# EasyEDA_SCH_ESPHome_Inverter_2341.net
KiCad netlist of a schematic drawn in EasyEDA
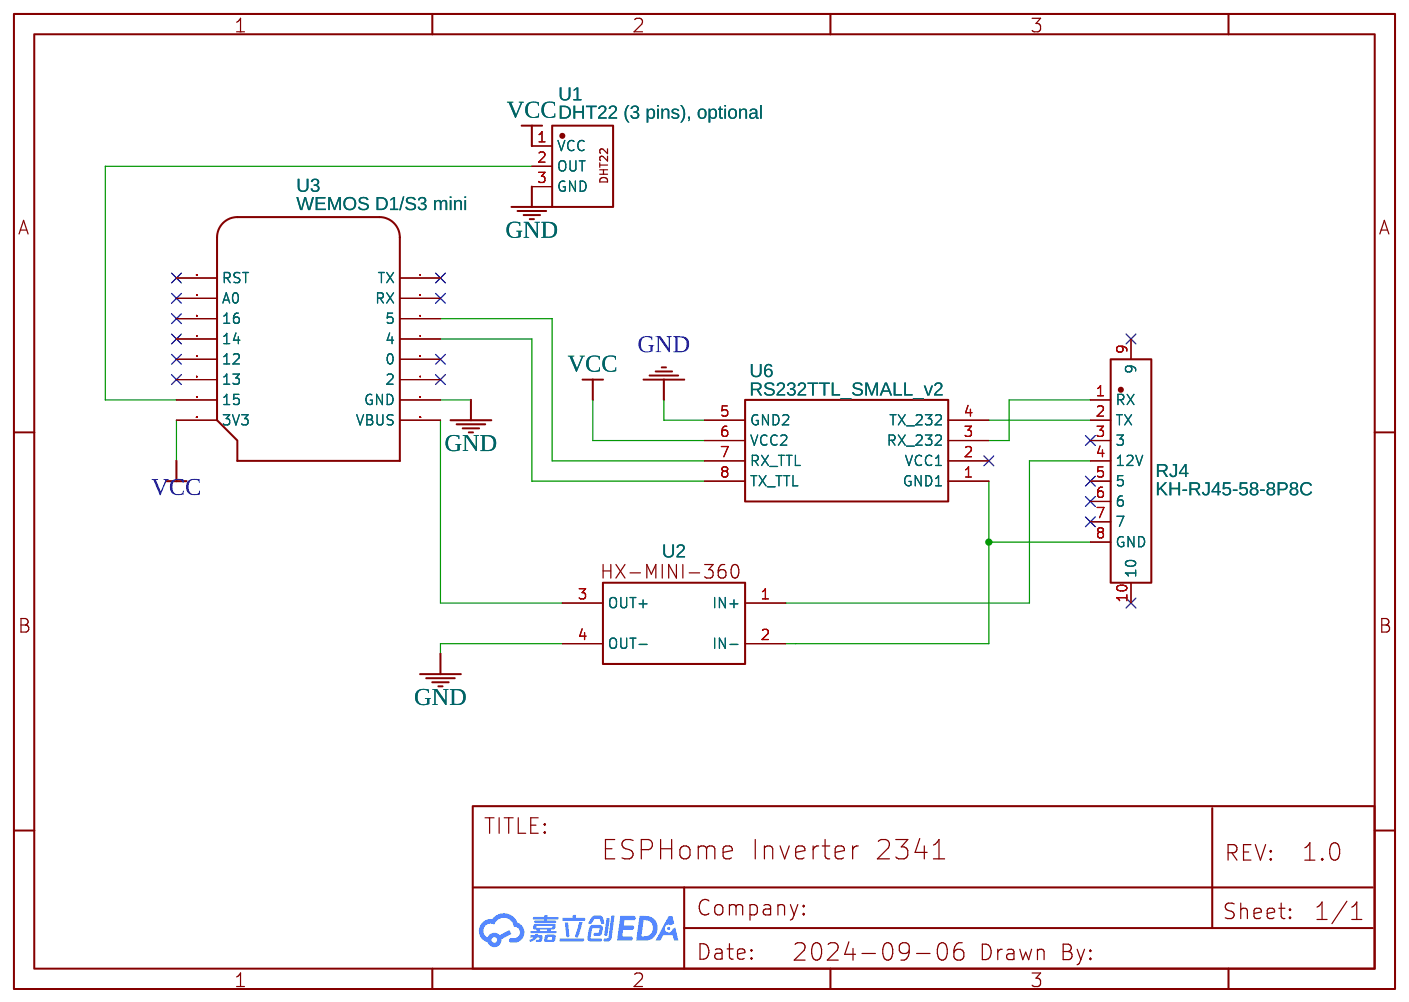
[diagram p0: schematic sheet]

(export (version "E")
  (design (tool "Eeschema 10.0.6"))
  (components
    (comp (ref "RJ4")
      (value "KH-RJ45-58-8P8C")
      (fields (field (name "Manufacturer") "kinghelm(金航标)"))
      (libsource (lib "") (part "KH-RJ45-58-8P8C"))
    )
    (comp (ref "U1")
      (value "DHT22 (3 pins), optional")
      (fields (field (name "Manufacturer Part") "DHT22 Modulo") (field (name "Manufacturer") "ASAIR AM2302"))
      (libsource (lib "") (part "DHT22 Modulo (3 pinos)"))
    )
    (comp (ref "U2") (value "HX-MINI-360 Module") (libsource (lib "") (part "HX-MINI-360 Module")))
    (comp (ref "U3")
      (value "WEMOS D1/S3 mini")
      (fields (field (name "Manufacturer Part") "WeMos D1 Mini Pro"))
      (libsource (lib "") (part "WEMOS D1 V4"))
    )
    (comp (ref "U6") (value "RS232TTL_SMALL_v2") (libsource (lib "") (part "RS232TTL_SMALL_v2")))
  )
  (nets
    (net (code "1") (name "GND") (class "Default")
      (node (ref "U1") (pin "3") (pinfunction "GND_3") (pintype "unspecified"))
      (node (ref "U2") (pin "4") (pinfunction "OUT-_4") (pintype "unspecified"))
      (node (ref "U3") (pin "GND") (pinfunction "GND_GND") (pintype "unspecified"))
      (node (ref "U6") (pin "5") (pinfunction "GND2_5") (pintype "unspecified"))
    )
    (net (code "2") (name "Net-(RJ4-12V)") (class "Default")
      (node (ref "RJ4") (pin "4") (pinfunction "12V_4") (pintype "unspecified"))
      (node (ref "U2") (pin "1") (pinfunction "IN+_1") (pintype "unspecified"))
    )
    (net (code "3") (name "Net-(RJ4-GND)") (class "Default")
      (node (ref "RJ4") (pin "8") (pinfunction "GND_8") (pintype "unspecified"))
      (node (ref "U2") (pin "2") (pinfunction "IN-_2") (pintype "unspecified"))
      (node (ref "U6") (pin "1") (pinfunction "GND1_1") (pintype "unspecified"))
    )
    (net (code "4") (name "Net-(RJ4-RX)") (class "Default")
      (node (ref "RJ4") (pin "1") (pinfunction "RX_1") (pintype "unspecified"))
      (node (ref "U6") (pin "3") (pinfunction "RX_232_3") (pintype "unspecified"))
    )
    (net (code "5") (name "Net-(RJ4-TX)") (class "Default")
      (node (ref "RJ4") (pin "2") (pinfunction "TX_2") (pintype "unspecified"))
      (node (ref "U6") (pin "4") (pinfunction "TX_232_4") (pintype "unspecified"))
    )
    (net (code "6") (name "Net-(U1-OUT)") (class "Default")
      (node (ref "U1") (pin "2") (pinfunction "OUT_2") (pintype "unspecified"))
      (node (ref "U3") (pin "15") (pinfunction "15_15") (pintype "unspecified"))
    )
    (net (code "7") (name "Net-(U2-OUT+)") (class "Default")
      (node (ref "U2") (pin "3") (pinfunction "OUT+_3") (pintype "unspecified"))
      (node (ref "U3") (pin "VBUS") (pinfunction "VBUS_VBUS") (pintype "unspecified"))
    )
    (net (code "8") (name "Net-(U6-RX_TTL)") (class "Default")
      (node (ref "U3") (pin "5") (pinfunction "5_5") (pintype "unspecified"))
      (node (ref "U6") (pin "7") (pinfunction "RX_TTL_7") (pintype "unspecified"))
    )
    (net (code "9") (name "Net-(U6-TX_TTL)") (class "Default")
      (node (ref "U3") (pin "4") (pinfunction "4_4") (pintype "unspecified"))
      (node (ref "U6") (pin "8") (pinfunction "TX_TTL_8") (pintype "unspecified"))
    )
    (net (code "10") (name "VCC") (class "Default")
      (node (ref "U1") (pin "1") (pinfunction "VCC_1") (pintype "unspecified"))
      (node (ref "U3") (pin "3V3") (pinfunction "3V3_3V3") (pintype "unspecified"))
      (node (ref "U6") (pin "6") (pinfunction "VCC2_6") (pintype "unspecified"))
    )
    (net (code "11") (name "unconnected-(RJ4-Pad3)") (class "Default")
      (node (ref "RJ4") (pin "3") (pinfunction "3_3") (pintype "unspecified+no_connect"))
    )
    (net (code "12") (name "unconnected-(RJ4-Pad5)") (class "Default")
      (node (ref "RJ4") (pin "5") (pinfunction "5_5") (pintype "unspecified+no_connect"))
    )
    (net (code "13") (name "unconnected-(RJ4-Pad6)") (class "Default")
      (node (ref "RJ4") (pin "6") (pinfunction "6_6") (pintype "unspecified+no_connect"))
    )
    (net (code "14") (name "unconnected-(RJ4-Pad7)") (class "Default")
      (node (ref "RJ4") (pin "7") (pinfunction "7_7") (pintype "unspecified+no_connect"))
    )
    (net (code "15") (name "unconnected-(RJ4-Pad9)") (class "Default")
      (node (ref "RJ4") (pin "9") (pinfunction "9_9") (pintype "unspecified+no_connect"))
    )
    (net (code "16") (name "unconnected-(RJ4-Pad10)") (class "Default")
      (node (ref "RJ4") (pin "10") (pinfunction "10_10") (pintype "unspecified+no_connect"))
    )
    (net (code "17") (name "unconnected-(U3-Pad0)") (class "Default")
      (node (ref "U3") (pin "0") (pinfunction "0_0") (pintype "unspecified+no_connect"))
    )
    (net (code "18") (name "unconnected-(U3-Pad2)") (class "Default")
      (node (ref "U3") (pin "2") (pinfunction "2_2") (pintype "unspecified+no_connect"))
    )
    (net (code "19") (name "unconnected-(U3-Pad12)") (class "Default")
      (node (ref "U3") (pin "12") (pinfunction "12_12") (pintype "unspecified+no_connect"))
    )
    (net (code "20") (name "unconnected-(U3-Pad13)") (class "Default")
      (node (ref "U3") (pin "13") (pinfunction "13_13") (pintype "unspecified+no_connect"))
    )
    (net (code "21") (name "unconnected-(U3-Pad14)") (class "Default")
      (node (ref "U3") (pin "14") (pinfunction "14_14") (pintype "unspecified+no_connect"))
    )
    (net (code "22") (name "unconnected-(U3-Pad16)") (class "Default")
      (node (ref "U3") (pin "16") (pinfunction "16_16") (pintype "unspecified+no_connect"))
    )
    (net (code "23") (name "unconnected-(U3-PadA0)") (class "Default")
      (node (ref "U3") (pin "A0") (pinfunction "A0_A0") (pintype "unspecified+no_connect"))
    )
    (net (code "24") (name "unconnected-(U3-PadRST)") (class "Default")
      (node (ref "U3") (pin "RST") (pinfunction "RST_RST") (pintype "unspecified+no_connect"))
    )
    (net (code "25") (name "unconnected-(U3-PadRX)") (class "Default")
      (node (ref "U3") (pin "RX") (pinfunction "RX_RX") (pintype "unspecified+no_connect"))
    )
    (net (code "26") (name "unconnected-(U3-PadTX)") (class "Default")
      (node (ref "U3") (pin "TX") (pinfunction "TX_TX") (pintype "unspecified+no_connect"))
    )
    (net (code "27") (name "unconnected-(U6-VCC1-Pad2)") (class "Default")
      (node (ref "U6") (pin "2") (pinfunction "VCC1_2") (pintype "unspecified+no_connect"))
    )
  )
)
